# Main_TopSheet.net
KiCad netlist of a schematic drawn in Altium Designer
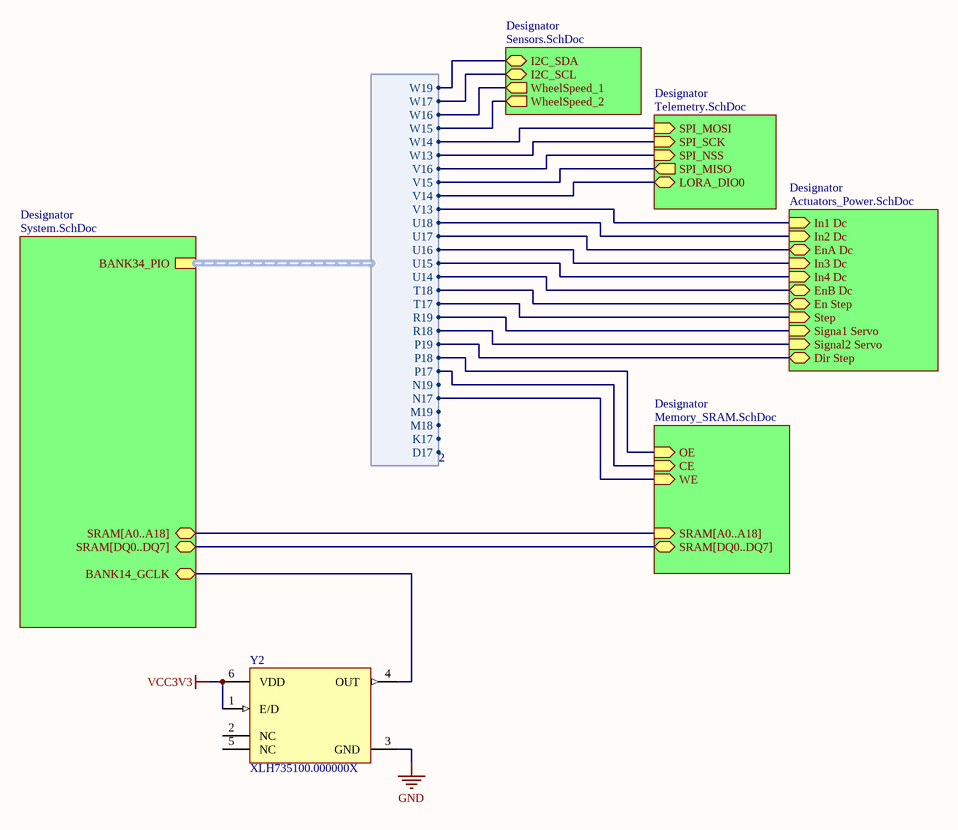
[diagram p0: Main_TopSheet.SchDoc]

(export (version "E")
  (design (tool "Eeschema 10.0.6"))
  (components
    (comp (ref "Y2")
      (value "XLH735100.000000X")
      (footprint "JU6_MFG")
      (description "Crystal ROHS3Compliant Enable/Disable Active Oscillator -20C~70C 47mA 0.055 1.40mm 100MHz")
      (libsource (lib "Altium Content Vault") (part "417ef702a4d54c7493ff5d4b63273bc"))
    )
  )
  (nets
    (net (code "2") (name "/BANK14_GCLK") (class "Default")
      (node (ref "Y2") (pin "4") (pinfunction "OUT_4") (pintype "output"))
    )
    (net (code "29") (name "GND") (class "Default")
      (node (ref "Y2") (pin "3") (pinfunction "GND_3") (pintype "power_in"))
    )
    (net (code "30") (name "VCC3V3") (class "Default")
      (node (ref "Y2") (pin "1") (pinfunction "E/D_1") (pintype "input"))
      (node (ref "Y2") (pin "6") (pinfunction "VDD_6") (pintype "power_in"))
    )
    (net (code "31") (name "unconnected-(Y2-NC-Pad2)") (class "Default")
      (node (ref "Y2") (pin "2") (pinfunction "NC_2") (pintype "passive"))
    )
    (net (code "32") (name "unconnected-(Y2-NC-Pad5)") (class "Default")
      (node (ref "Y2") (pin "5") (pinfunction "NC_5") (pintype "passive"))
    )
  )
)
